# pinoccio-wifi.net
KiCad netlist of a schematic drawn in EAGLE
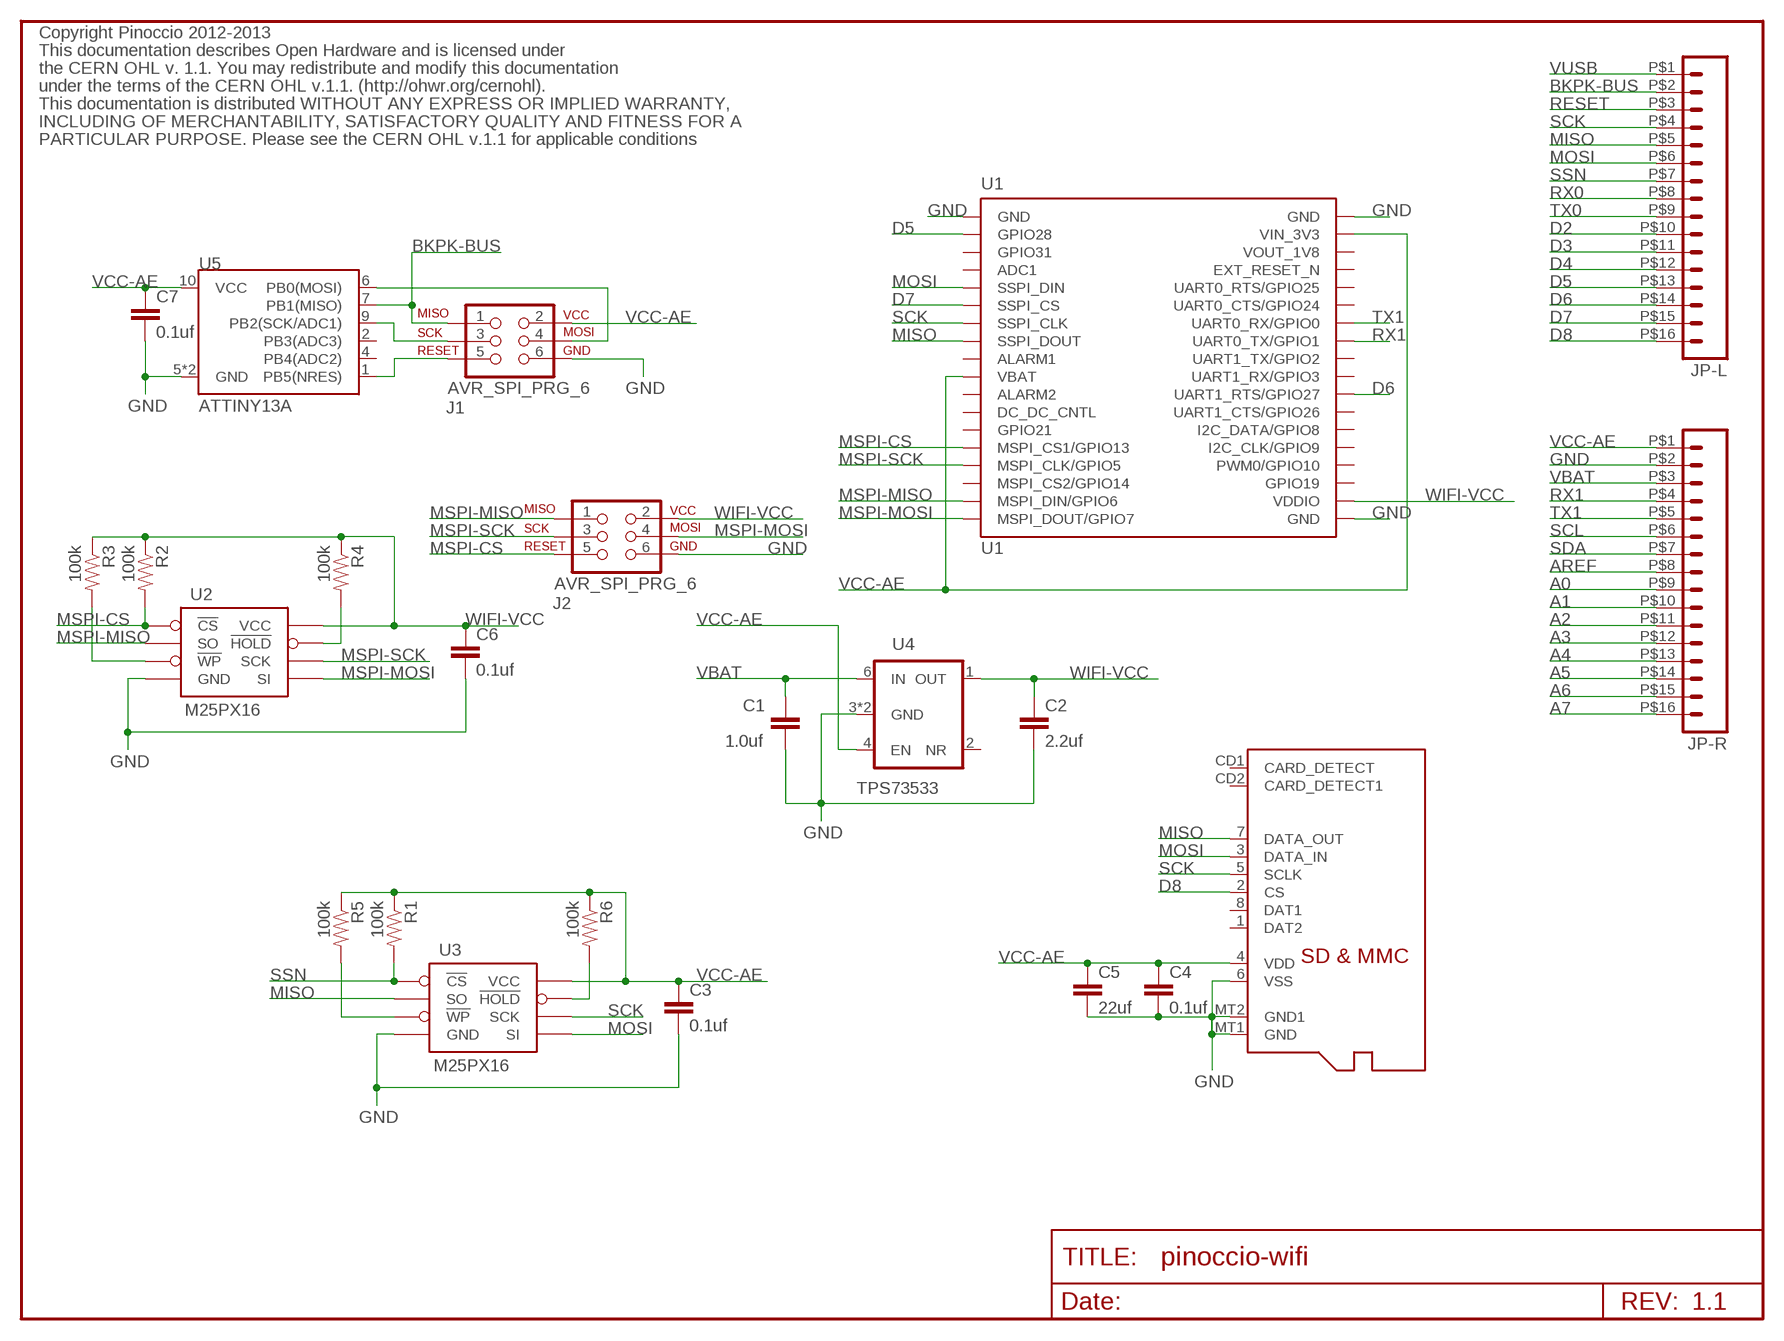
[diagram p0: schematic, sheet 1]

(export (version "E")
  (design (tool "Eeschema 10.0.6"))
  (components
    (comp (ref "C1")
      (value "1.0uf")
      (footprint "eagle-import:0402-CAP")
      (libsource (lib "eagle-import") (part "CAP0402-CAP"))
    )
    (comp (ref "C2")
      (value "2.2uf")
      (footprint "eagle-import:0402-CAP")
      (libsource (lib "eagle-import") (part "CAP0402-CAP"))
    )
    (comp (ref "C3")
      (value "0.1uf")
      (footprint "eagle-import:0402-CAP")
      (libsource (lib "eagle-import") (part "CAP0402-CAP"))
    )
    (comp (ref "C4")
      (value "0.1uf")
      (footprint "eagle-import:0402-CAP")
      (libsource (lib "eagle-import") (part "CAP0402-CAP"))
    )
    (comp (ref "C5")
      (value "22uf")
      (footprint "eagle-import:0603-CAP")
      (libsource (lib "eagle-import") (part "CAP0603-CAP"))
    )
    (comp (ref "C6")
      (value "0.1uf")
      (footprint "eagle-import:0402-CAP")
      (libsource (lib "eagle-import") (part "CAP0402-CAP"))
    )
    (comp (ref "C7")
      (value "0.1uf")
      (footprint "eagle-import:0402-CAP")
      (libsource (lib "eagle-import") (part "CAP0402-CAP"))
    )
    (comp (ref "J1")
      (value "AVR_SPI_PRG_6")
      (footprint "eagle-import:2X3-PAD")
      (libsource (lib "eagle-import") (part "AVR_SPI_PRG_6"))
    )
    (comp (ref "J2")
      (value "AVR_SPI_PRG_6")
      (footprint "eagle-import:2X3-PAD")
      (libsource (lib "eagle-import") (part "AVR_SPI_PRG_6"))
    )
    (comp (ref "JP-L")
      (value "M162MM")
      (footprint "eagle-import:1X16_2MM")
      (libsource (lib "eagle-import") (part "M162MM"))
    )
    (comp (ref "JP-R")
      (value "M162MM")
      (footprint "eagle-import:1X16_2MM")
      (libsource (lib "eagle-import") (part "M162MM"))
    )
    (comp (ref "R1")
      (value "100k")
      (footprint "eagle-import:0402-RES")
      (libsource (lib "eagle-import") (part "RESISTOR0402-RES"))
    )
    (comp (ref "R2")
      (value "100k")
      (footprint "eagle-import:0402-RES")
      (libsource (lib "eagle-import") (part "RESISTOR0402-RES"))
    )
    (comp (ref "R3")
      (value "100k")
      (footprint "eagle-import:0402-RES")
      (libsource (lib "eagle-import") (part "RESISTOR0402-RES"))
    )
    (comp (ref "R4")
      (value "100k")
      (footprint "eagle-import:0402-RES")
      (libsource (lib "eagle-import") (part "RESISTOR0402-RES"))
    )
    (comp (ref "R5")
      (value "100k")
      (footprint "eagle-import:0402-RES")
      (libsource (lib "eagle-import") (part "RESISTOR0402-RES"))
    )
    (comp (ref "R6")
      (value "100k")
      (footprint "eagle-import:0402-RES")
      (libsource (lib "eagle-import") (part "RESISTOR0402-RES"))
    )
    (comp (ref "U$1")
      (value "MICROSD")
      (footprint "eagle-import:MICROSD")
      (libsource (lib "eagle-import") (part "MICROSD"))
    )
    (comp (ref "U1")
      (value "GS1011MIPS")
      (footprint "eagle-import:GS1011MIPS")
      (libsource (lib "eagle-import") (part "GS1011MIPS"))
    )
    (comp (ref "U2")
      (value "M25PX16")
      (footprint "eagle-import:SO8N")
      (libsource (lib "eagle-import") (part "M25PX16SO8N"))
    )
    (comp (ref "U3")
      (value "M25PX16")
      (footprint "eagle-import:SO8N")
      (libsource (lib "eagle-import") (part "M25PX16SO8N"))
    )
    (comp (ref "U4")
      (value "TPS73533")
      (footprint "eagle-import:SON-6-DRV")
      (libsource (lib "eagle-import") (part "LDO-TPS73533"))
    )
    (comp (ref "U5")
      (value "ATTINY13A")
      (footprint "eagle-import:QFN-10")
      (libsource (lib "eagle-import") (part "ATTINY13QFN10"))
    )
  )
  (nets
    (net (code "1") (name "/A0") (class "Default")
      (node (ref "JP-R") (pin "P$9") (pinfunction "9_P$9") (pintype "passive"))
    )
    (net (code "2") (name "/A1") (class "Default")
      (node (ref "JP-R") (pin "P$10") (pinfunction "10_P$10") (pintype "passive"))
    )
    (net (code "3") (name "/A2") (class "Default")
      (node (ref "JP-R") (pin "P$11") (pinfunction "11_P$11") (pintype "passive"))
    )
    (net (code "4") (name "/A3") (class "Default")
      (node (ref "JP-R") (pin "P$12") (pinfunction "12_P$12") (pintype "passive"))
    )
    (net (code "5") (name "/A4") (class "Default")
      (node (ref "JP-R") (pin "P$13") (pinfunction "13_P$13") (pintype "passive"))
    )
    (net (code "6") (name "/A5") (class "Default")
      (node (ref "JP-R") (pin "P$14") (pinfunction "14_P$14") (pintype "passive"))
    )
    (net (code "7") (name "/A6") (class "Default")
      (node (ref "JP-R") (pin "P$15") (pinfunction "15_P$15") (pintype "passive"))
    )
    (net (code "8") (name "/A7") (class "Default")
      (node (ref "JP-R") (pin "P$16") (pinfunction "16_P$16") (pintype "passive"))
    )
    (net (code "9") (name "/AREF") (class "Default")
      (node (ref "JP-R") (pin "P$8") (pinfunction "8_P$8") (pintype "passive"))
    )
    (net (code "10") (name "/BKPK-BUS") (class "Default")
      (node (ref "J1") (pin "1") (pinfunction "1_1") (pintype "passive"))
      (node (ref "JP-L") (pin "P$2") (pinfunction "2_P$2") (pintype "passive"))
      (node (ref "U5") (pin "7") (pinfunction "PB1(MISO)_7") (pintype "bidirectional"))
    )
    (net (code "11") (name "/D2") (class "Default")
      (node (ref "JP-L") (pin "P$10") (pinfunction "10_P$10") (pintype "passive"))
    )
    (net (code "12") (name "/D3") (class "Default")
      (node (ref "JP-L") (pin "P$11") (pinfunction "11_P$11") (pintype "passive"))
    )
    (net (code "13") (name "/D4") (class "Default")
      (node (ref "JP-L") (pin "P$12") (pinfunction "12_P$12") (pintype "passive"))
    )
    (net (code "14") (name "/D5") (class "Default")
      (node (ref "JP-L") (pin "P$13") (pinfunction "13_P$13") (pintype "passive"))
      (node (ref "U1") (pin "P$2") (pinfunction "GPIO28_P$2") (pintype "bidirectional"))
    )
    (net (code "15") (name "/D6") (class "Default")
      (node (ref "JP-L") (pin "P$14") (pinfunction "14_P$14") (pintype "passive"))
      (node (ref "U1") (pin "P$26") (pinfunction "UART1_RTS/GPIO27_P$26") (pintype "bidirectional"))
    )
    (net (code "16") (name "/D7") (class "Default")
      (node (ref "JP-L") (pin "P$15") (pinfunction "15_P$15") (pintype "passive"))
      (node (ref "U1") (pin "P$6") (pinfunction "SSPI_CS_P$6") (pintype "bidirectional"))
    )
    (net (code "17") (name "/D8") (class "Default")
      (node (ref "JP-L") (pin "P$16") (pinfunction "16_P$16") (pintype "passive"))
      (node (ref "U$1") (pin "2") (pinfunction "CS_2") (pintype "input"))
    )
    (net (code "18") (name "/GND") (class "Default")
      (node (ref "C1") (pin "2") (pinfunction "2_2") (pintype "passive"))
      (node (ref "C2") (pin "2") (pinfunction "2_2") (pintype "passive"))
      (node (ref "C3") (pin "2") (pinfunction "2_2") (pintype "passive"))
      (node (ref "C4") (pin "2") (pinfunction "2_2") (pintype "passive"))
      (node (ref "C5") (pin "2") (pinfunction "2_2") (pintype "passive"))
      (node (ref "C6") (pin "2") (pinfunction "2_2") (pintype "passive"))
      (node (ref "C7") (pin "2") (pinfunction "2_2") (pintype "passive"))
      (node (ref "J1") (pin "6") (pinfunction "6_6") (pintype "passive"))
      (node (ref "J2") (pin "6") (pinfunction "6_6") (pintype "passive"))
      (node (ref "JP-R") (pin "P$2") (pinfunction "2_P$2") (pintype "passive"))
      (node (ref "U$1") (pin "6") (pinfunction "VSS_6") (pintype "power_in"))
      (node (ref "U$1") (pin "MT1") (pinfunction "GND_MT1") (pintype "power_in"))
      (node (ref "U$1") (pin "MT2") (pinfunction "GND1_MT2") (pintype "power_in"))
      (node (ref "U1") (pin "P$1") (pinfunction "GND_P$1") (pintype "bidirectional"))
      (node (ref "U1") (pin "P$19") (pinfunction "GND_P$19") (pintype "bidirectional"))
      (node (ref "U1") (pin "P$36") (pinfunction "GND_P$36") (pintype "bidirectional"))
      (node (ref "U2") (pin "4") (pinfunction "GND_4") (pintype "bidirectional"))
      (node (ref "U3") (pin "4") (pinfunction "GND_4") (pintype "bidirectional"))
      (node (ref "U4") (pin "3") (pinfunction "GND_3") (pintype "input"))
      (node (ref "U4") (pin "PAD") (pinfunction "GND_PAD") (pintype "input"))
      (node (ref "U5") (pin "5") (pinfunction "GND_5") (pintype "bidirectional"))
      (node (ref "U5") (pin "EP") (pinfunction "GND_EP") (pintype "bidirectional"))
    )
    (net (code "19") (name "/MISO") (class "Default")
      (node (ref "JP-L") (pin "P$5") (pinfunction "5_P$5") (pintype "passive"))
      (node (ref "U$1") (pin "7") (pinfunction "DATA_OUT_7") (pintype "output"))
      (node (ref "U1") (pin "P$8") (pinfunction "SSPI_DOUT_P$8") (pintype "bidirectional"))
      (node (ref "U3") (pin "2") (pinfunction "SO_2") (pintype "bidirectional"))
    )
    (net (code "20") (name "/MOSI") (class "Default")
      (node (ref "JP-L") (pin "P$6") (pinfunction "6_P$6") (pintype "passive"))
      (node (ref "U$1") (pin "3") (pinfunction "DATA_IN_3") (pintype "input"))
      (node (ref "U1") (pin "P$5") (pinfunction "SSPI_DIN_P$5") (pintype "bidirectional"))
      (node (ref "U3") (pin "5") (pinfunction "SI_5") (pintype "bidirectional"))
    )
    (net (code "21") (name "/MSPI-CS") (class "Default")
      (node (ref "J2") (pin "5") (pinfunction "5_5") (pintype "passive"))
      (node (ref "R2") (pin "2") (pinfunction "2_2") (pintype "passive"))
      (node (ref "U1") (pin "P$14") (pinfunction "MSPI_CS1/GPIO13_P$14") (pintype "bidirectional"))
      (node (ref "U2") (pin "1") (pinfunction "~{CS}_1") (pintype "bidirectional"))
    )
    (net (code "22") (name "/MSPI-MISO") (class "Default")
      (node (ref "J2") (pin "1") (pinfunction "1_1") (pintype "passive"))
      (node (ref "U1") (pin "P$17") (pinfunction "MSPI_DIN/GPIO6_P$17") (pintype "bidirectional"))
      (node (ref "U2") (pin "2") (pinfunction "SO_2") (pintype "bidirectional"))
    )
    (net (code "23") (name "/MSPI-MOSI") (class "Default")
      (node (ref "J2") (pin "4") (pinfunction "4_4") (pintype "passive"))
      (node (ref "U1") (pin "P$18") (pinfunction "MSPI_DOUT/GPIO7_P$18") (pintype "bidirectional"))
      (node (ref "U2") (pin "5") (pinfunction "SI_5") (pintype "bidirectional"))
    )
    (net (code "24") (name "/MSPI-SCK") (class "Default")
      (node (ref "J2") (pin "3") (pinfunction "3_3") (pintype "passive"))
      (node (ref "U1") (pin "P$15") (pinfunction "MSPI_CLK/GPIO5_P$15") (pintype "bidirectional"))
      (node (ref "U2") (pin "6") (pinfunction "SCK_6") (pintype "bidirectional"))
    )
    (net (code "25") (name "/RESET") (class "Default")
      (node (ref "JP-L") (pin "P$3") (pinfunction "3_P$3") (pintype "passive"))
    )
    (net (code "26") (name "/RX0") (class "Default")
      (node (ref "JP-L") (pin "P$8") (pinfunction "8_P$8") (pintype "passive"))
    )
    (net (code "27") (name "/RX1") (class "Default")
      (node (ref "JP-R") (pin "P$4") (pinfunction "4_P$4") (pintype "passive"))
      (node (ref "U1") (pin "P$29") (pinfunction "UART0_TX/GPIO1_P$29") (pintype "bidirectional"))
    )
    (net (code "28") (name "/SCK") (class "Default")
      (node (ref "JP-L") (pin "P$4") (pinfunction "4_P$4") (pintype "passive"))
      (node (ref "U$1") (pin "5") (pinfunction "SCLK_5") (pintype "input"))
      (node (ref "U1") (pin "P$7") (pinfunction "SSPI_CLK_P$7") (pintype "bidirectional"))
      (node (ref "U3") (pin "6") (pinfunction "SCK_6") (pintype "bidirectional"))
    )
    (net (code "29") (name "/SCL") (class "Default")
      (node (ref "JP-R") (pin "P$6") (pinfunction "6_P$6") (pintype "passive"))
    )
    (net (code "30") (name "/SDA") (class "Default")
      (node (ref "JP-R") (pin "P$7") (pinfunction "7_P$7") (pintype "passive"))
    )
    (net (code "31") (name "/SSN") (class "Default")
      (node (ref "JP-L") (pin "P$7") (pinfunction "7_P$7") (pintype "passive"))
      (node (ref "R1") (pin "2") (pinfunction "2_2") (pintype "passive"))
      (node (ref "U3") (pin "1") (pinfunction "~{CS}_1") (pintype "bidirectional"))
    )
    (net (code "32") (name "/TX0") (class "Default")
      (node (ref "JP-L") (pin "P$9") (pinfunction "9_P$9") (pintype "passive"))
    )
    (net (code "33") (name "/TX1") (class "Default")
      (node (ref "JP-R") (pin "P$5") (pinfunction "5_P$5") (pintype "passive"))
      (node (ref "U1") (pin "P$30") (pinfunction "UART0_RX/GPIO0_P$30") (pintype "bidirectional"))
    )
    (net (code "34") (name "/VBAT") (class "Default")
      (node (ref "C1") (pin "1") (pinfunction "1_1") (pintype "passive"))
      (node (ref "JP-R") (pin "P$3") (pinfunction "3_P$3") (pintype "passive"))
      (node (ref "U4") (pin "6") (pinfunction "IN_6") (pintype "input"))
    )
    (net (code "35") (name "/VCC-AE") (class "Default")
      (node (ref "C3") (pin "1") (pinfunction "1_1") (pintype "passive"))
      (node (ref "C4") (pin "1") (pinfunction "1_1") (pintype "passive"))
      (node (ref "C5") (pin "1") (pinfunction "1_1") (pintype "passive"))
      (node (ref "C7") (pin "1") (pinfunction "1_1") (pintype "passive"))
      (node (ref "J1") (pin "2") (pinfunction "2_2") (pintype "passive"))
      (node (ref "JP-R") (pin "P$1") (pinfunction "1_P$1") (pintype "passive"))
      (node (ref "R1") (pin "1") (pinfunction "1_1") (pintype "passive"))
      (node (ref "R5") (pin "1") (pinfunction "1_1") (pintype "passive"))
      (node (ref "R6") (pin "1") (pinfunction "1_1") (pintype "passive"))
      (node (ref "U$1") (pin "4") (pinfunction "VDD_4") (pintype "power_in"))
      (node (ref "U1") (pin "P$10") (pinfunction "VBAT_P$10") (pintype "bidirectional"))
      (node (ref "U1") (pin "P$35") (pinfunction "VIN_3V3_P$35") (pintype "bidirectional"))
      (node (ref "U3") (pin "8") (pinfunction "VCC_8") (pintype "bidirectional"))
      (node (ref "U4") (pin "4") (pinfunction "EN_4") (pintype "input"))
      (node (ref "U5") (pin "10") (pinfunction "VCC_10") (pintype "bidirectional"))
    )
    (net (code "36") (name "/VUSB") (class "Default")
      (node (ref "JP-L") (pin "P$1") (pinfunction "1_P$1") (pintype "passive"))
    )
    (net (code "37") (name "/WIFI-VCC") (class "Default")
      (node (ref "C2") (pin "1") (pinfunction "1_1") (pintype "passive"))
      (node (ref "C6") (pin "1") (pinfunction "1_1") (pintype "passive"))
      (node (ref "J2") (pin "2") (pinfunction "2_2") (pintype "passive"))
      (node (ref "R2") (pin "1") (pinfunction "1_1") (pintype "passive"))
      (node (ref "R3") (pin "1") (pinfunction "1_1") (pintype "passive"))
      (node (ref "R4") (pin "1") (pinfunction "1_1") (pintype "passive"))
      (node (ref "U1") (pin "P$20") (pinfunction "VDDIO_P$20") (pintype "bidirectional"))
      (node (ref "U2") (pin "8") (pinfunction "VCC_8") (pintype "bidirectional"))
      (node (ref "U4") (pin "1") (pinfunction "OUT_1") (pintype "power_in"))
    )
    (net (code "38") (name "Net-(U2-~{HOLD})") (class "Default")
      (node (ref "R4") (pin "2") (pinfunction "2_2") (pintype "passive"))
      (node (ref "U2") (pin "7") (pinfunction "~{HOLD}_7") (pintype "bidirectional"))
    )
    (net (code "39") (name "Net-(U2-~{WP})") (class "Default")
      (node (ref "R3") (pin "2") (pinfunction "2_2") (pintype "passive"))
      (node (ref "U2") (pin "3") (pinfunction "~{WP}_3") (pintype "bidirectional"))
    )
    (net (code "40") (name "Net-(U3-~{HOLD})") (class "Default")
      (node (ref "R6") (pin "2") (pinfunction "2_2") (pintype "passive"))
      (node (ref "U3") (pin "7") (pinfunction "~{HOLD}_7") (pintype "bidirectional"))
    )
    (net (code "41") (name "Net-(U3-~{WP})") (class "Default")
      (node (ref "R5") (pin "2") (pinfunction "2_2") (pintype "passive"))
      (node (ref "U3") (pin "3") (pinfunction "~{WP}_3") (pintype "bidirectional"))
    )
    (net (code "42") (name "Net-(U5-PB0(MOSI))") (class "Default")
      (node (ref "J1") (pin "4") (pinfunction "4_4") (pintype "passive"))
      (node (ref "U5") (pin "6") (pinfunction "PB0(MOSI)_6") (pintype "bidirectional"))
    )
    (net (code "43") (name "Net-(U5-PB2(SCK{slash}ADC1))") (class "Default")
      (node (ref "J1") (pin "3") (pinfunction "3_3") (pintype "passive"))
      (node (ref "U5") (pin "9") (pinfunction "PB2(SCK/ADC1)_9") (pintype "bidirectional"))
    )
    (net (code "44") (name "Net-(U5-PB5(NRES))") (class "Default")
      (node (ref "J1") (pin "5") (pinfunction "5_5") (pintype "passive"))
      (node (ref "U5") (pin "1") (pinfunction "PB5(NRES)_1") (pintype "bidirectional"))
    )
    (net (code "45") (name "unconnected-(U$1-CARD_DETECT-PadCD1)") (class "Default")
      (node (ref "U$1") (pin "CD1") (pinfunction "CARD_DETECT_CD1") (pintype "passive"))
    )
    (net (code "46") (name "unconnected-(U$1-CARD_DETECT1-PadCD2)") (class "Default")
      (node (ref "U$1") (pin "CD2") (pinfunction "CARD_DETECT1_CD2") (pintype "passive"))
    )
    (net (code "47") (name "unconnected-(U$1-DAT1-Pad8)") (class "Default")
      (node (ref "U$1") (pin "8") (pinfunction "DAT1_8") (pintype "bidirectional"))
    )
    (net (code "48") (name "unconnected-(U$1-DAT2-Pad1)") (class "Default")
      (node (ref "U$1") (pin "1") (pinfunction "DAT2_1") (pintype "bidirectional"))
    )
    (net (code "49") (name "unconnected-(U1-ADC1-PadP$4)") (class "Default")
      (node (ref "U1") (pin "P$4") (pinfunction "ADC1_P$4") (pintype "bidirectional"))
    )
    (net (code "50") (name "unconnected-(U1-ALARM1-PadP$9)") (class "Default")
      (node (ref "U1") (pin "P$9") (pinfunction "ALARM1_P$9") (pintype "bidirectional"))
    )
    (net (code "51") (name "unconnected-(U1-ALARM2-PadP$11)") (class "Default")
      (node (ref "U1") (pin "P$11") (pinfunction "ALARM2_P$11") (pintype "bidirectional"))
    )
    (net (code "52") (name "unconnected-(U1-DC_DC_CNTL-PadP$12)") (class "Default")
      (node (ref "U1") (pin "P$12") (pinfunction "DC_DC_CNTL_P$12") (pintype "bidirectional"))
    )
    (net (code "53") (name "unconnected-(U1-EXT_RESET_N-PadP$33)") (class "Default")
      (node (ref "U1") (pin "P$33") (pinfunction "EXT_RESET_N_P$33") (pintype "bidirectional"))
    )
    (net (code "54") (name "unconnected-(U1-GPIO19-PadP$21)") (class "Default")
      (node (ref "U1") (pin "P$21") (pinfunction "GPIO19_P$21") (pintype "bidirectional"))
    )
    (net (code "55") (name "unconnected-(U1-GPIO21-PadP$13)") (class "Default")
      (node (ref "U1") (pin "P$13") (pinfunction "GPIO21_P$13") (pintype "bidirectional"))
    )
    (net (code "56") (name "unconnected-(U1-GPIO31-PadP$3)") (class "Default")
      (node (ref "U1") (pin "P$3") (pinfunction "GPIO31_P$3") (pintype "bidirectional"))
    )
    (net (code "57") (name "unconnected-(U1-I2C_CLK{slash}GPIO9-PadP$23)") (class "Default")
      (node (ref "U1") (pin "P$23") (pinfunction "I2C_CLK/GPIO9_P$23") (pintype "bidirectional"))
    )
    (net (code "58") (name "unconnected-(U1-I2C_DATA{slash}GPIO8-PadP$24)") (class "Default")
      (node (ref "U1") (pin "P$24") (pinfunction "I2C_DATA/GPIO8_P$24") (pintype "bidirectional"))
    )
    (net (code "59") (name "unconnected-(U1-MSPI_CS2{slash}GPIO14-PadP$16)") (class "Default")
      (node (ref "U1") (pin "P$16") (pinfunction "MSPI_CS2/GPIO14_P$16") (pintype "bidirectional"))
    )
    (net (code "60") (name "unconnected-(U1-PWM0{slash}GPIO10-PadP$22)") (class "Default")
      (node (ref "U1") (pin "P$22") (pinfunction "PWM0/GPIO10_P$22") (pintype "bidirectional"))
    )
    (net (code "61") (name "unconnected-(U1-UART0_CTS{slash}GPIO24-PadP$31)") (class "Default")
      (node (ref "U1") (pin "P$31") (pinfunction "UART0_CTS/GPIO24_P$31") (pintype "bidirectional"))
    )
    (net (code "62") (name "unconnected-(U1-UART0_RTS{slash}GPIO25-PadP$32)") (class "Default")
      (node (ref "U1") (pin "P$32") (pinfunction "UART0_RTS/GPIO25_P$32") (pintype "bidirectional"))
    )
    (net (code "63") (name "unconnected-(U1-UART1_CTS{slash}GPIO26-PadP$25)") (class "Default")
      (node (ref "U1") (pin "P$25") (pinfunction "UART1_CTS/GPIO26_P$25") (pintype "bidirectional"))
    )
    (net (code "64") (name "unconnected-(U1-UART1_RX{slash}GPIO3-PadP$27)") (class "Default")
      (node (ref "U1") (pin "P$27") (pinfunction "UART1_RX/GPIO3_P$27") (pintype "bidirectional"))
    )
    (net (code "65") (name "unconnected-(U1-UART1_TX{slash}GPIO2-PadP$28)") (class "Default")
      (node (ref "U1") (pin "P$28") (pinfunction "UART1_TX/GPIO2_P$28") (pintype "bidirectional"))
    )
    (net (code "66") (name "unconnected-(U1-VOUT_1V8-PadP$34)") (class "Default")
      (node (ref "U1") (pin "P$34") (pinfunction "VOUT_1V8_P$34") (pintype "bidirectional"))
    )
    (net (code "67") (name "unconnected-(U4-NR-Pad2)") (class "Default")
      (node (ref "U4") (pin "2") (pinfunction "NR_2") (pintype "output"))
    )
    (net (code "68") (name "unconnected-(U4-N{slash}C-Pad5)") (class "Default")
      (node (ref "U4") (pin "5") (pinfunction "N/C_5") (pintype "no_connect"))
    )
    (net (code "69") (name "unconnected-(U5-PB3(ADC3)-Pad2)") (class "Default")
      (node (ref "U5") (pin "2") (pinfunction "PB3(ADC3)_2") (pintype "bidirectional"))
    )
    (net (code "70") (name "unconnected-(U5-PB4(ADC2)-Pad4)") (class "Default")
      (node (ref "U5") (pin "4") (pinfunction "PB4(ADC2)_4") (pintype "bidirectional"))
    )
  )
)
